# MegaShield-SMD.net
KiCad netlist of a schematic drawn in EAGLE
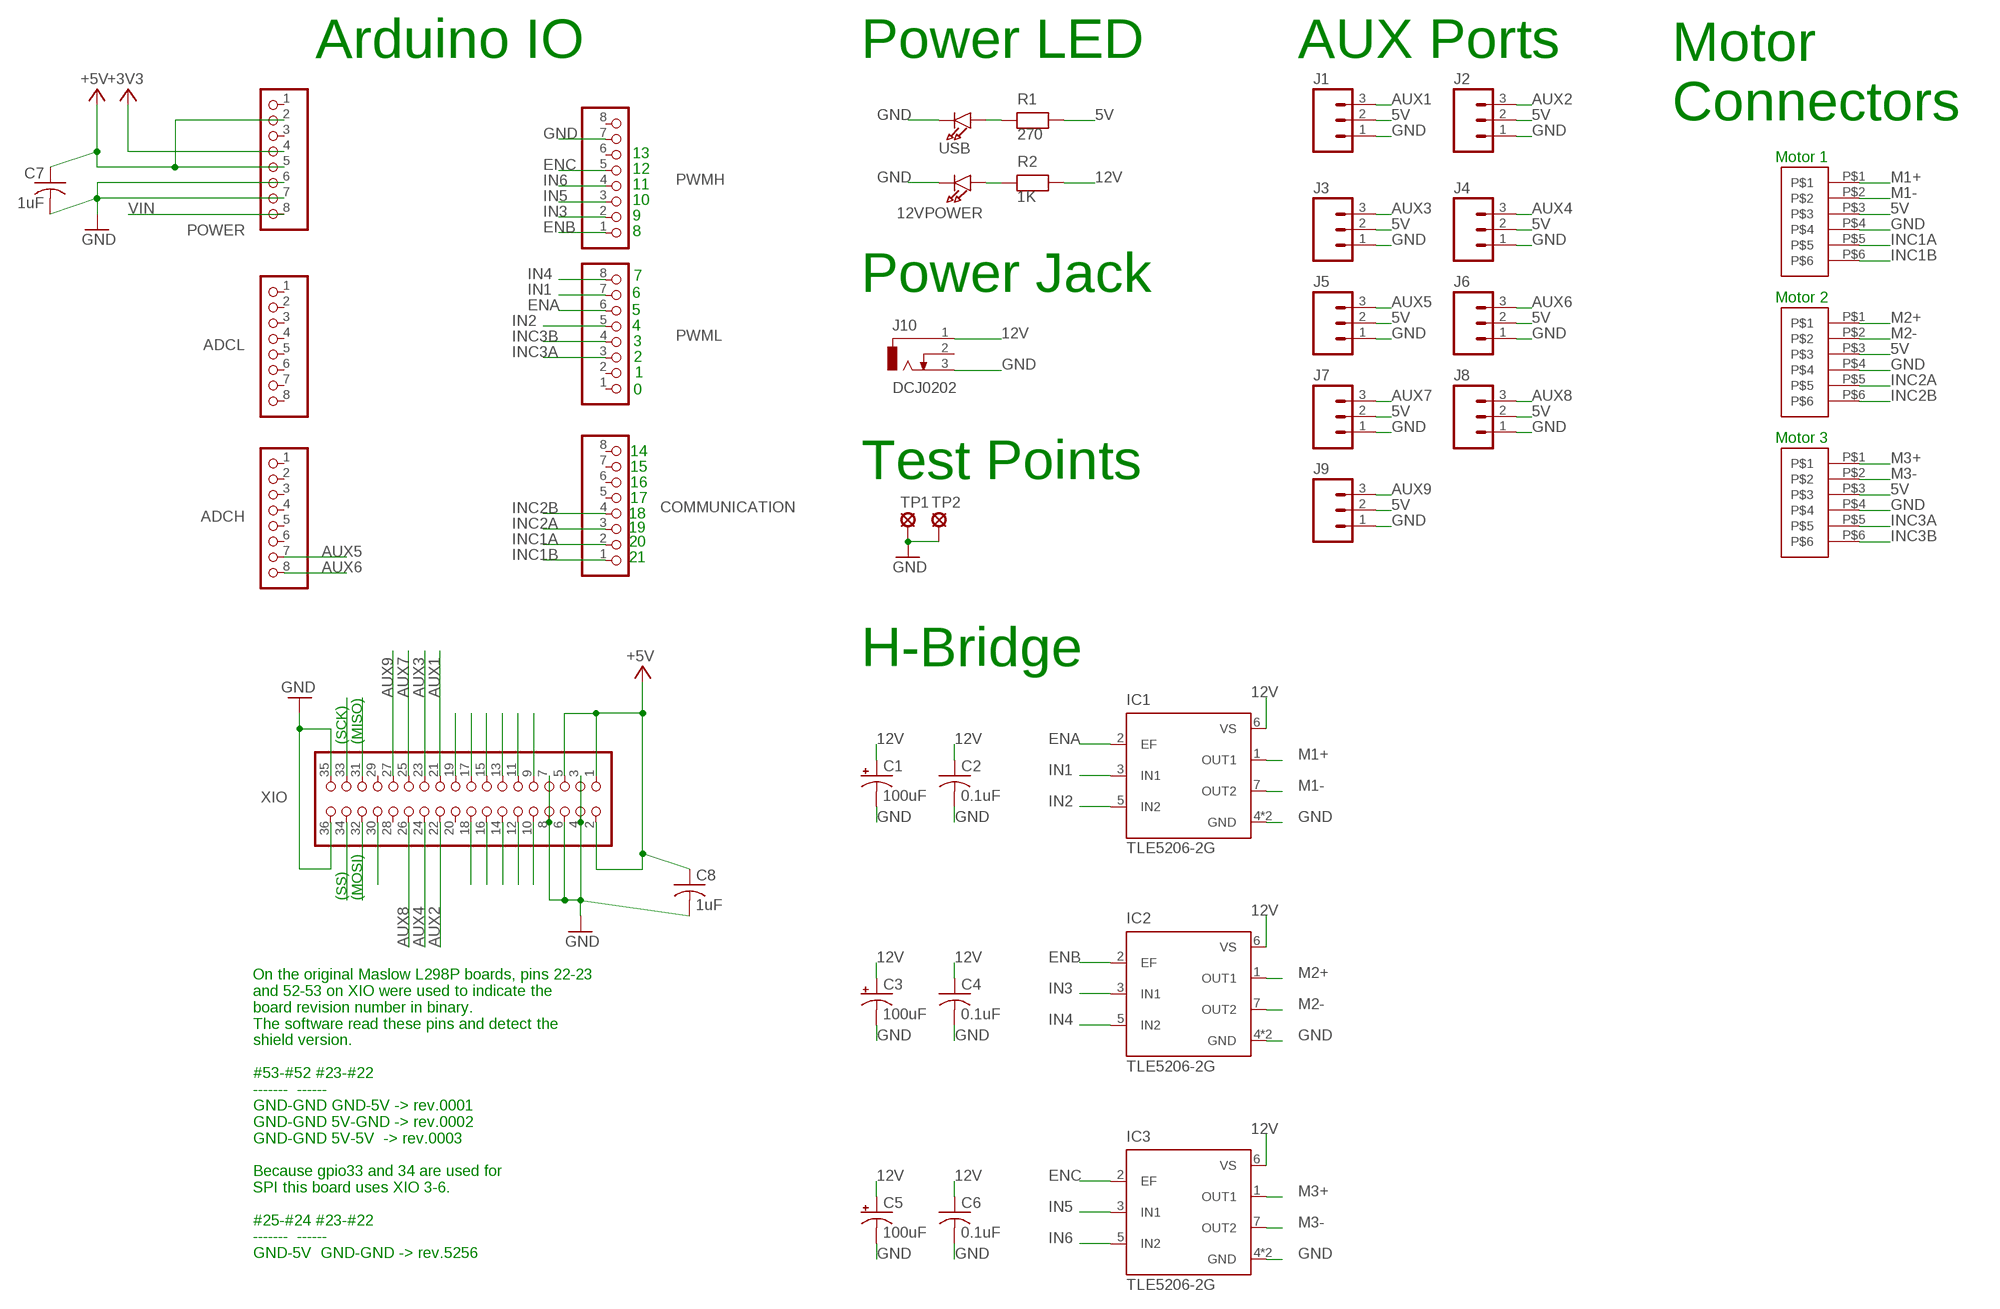
[diagram p0: schematic, sheet 1]

(export (version "E")
  (design (tool "Eeschema 10.0.6"))
  (components
    (comp (ref "12VPOWER")
      (value "LED1206")
      (footprint "eagle-import:CHIPLED_1206")
      (libsource (lib "eagle-import") (part "LED1206"))
    )
    (comp (ref "ADCH")
      (value "8x1F-H8.5")
      (footprint "eagle-import:1X08")
      (libsource (lib "eagle-import") (part "PINHD-1X8"))
    )
    (comp (ref "ADCL")
      (value "PINHD-1X8")
      (footprint "eagle-import:1X08")
      (libsource (lib "eagle-import") (part "pinhead_PINHD-1X8"))
    )
    (comp (ref "C1")
      (value "100uF")
      (footprint "eagle-import:PANASONIC_E")
      (libsource (lib "eagle-import") (part "CAP_POLE"))
    )
    (comp (ref "C2")
      (value "0.1uF")
      (footprint "eagle-import:C0805K")
      (libsource (lib "eagle-import") (part "C-USC0805K"))
    )
    (comp (ref "C3")
      (value "100uF")
      (footprint "eagle-import:PANASONIC_E")
      (libsource (lib "eagle-import") (part "CAP_POLE"))
    )
    (comp (ref "C4")
      (value "0.1uF")
      (footprint "eagle-import:C0805K")
      (libsource (lib "eagle-import") (part "C-USC0805K"))
    )
    (comp (ref "C5")
      (value "100uF")
      (footprint "eagle-import:PANASONIC_E")
      (libsource (lib "eagle-import") (part "CAP_POLE"))
    )
    (comp (ref "C6")
      (value "0.1uF")
      (footprint "eagle-import:C0805K")
      (libsource (lib "eagle-import") (part "C-USC0805K"))
    )
    (comp (ref "C7")
      (value "1uF")
      (footprint "eagle-import:C0805K")
      (libsource (lib "eagle-import") (part "C-USC0805K"))
    )
    (comp (ref "C8")
      (value "1uF")
      (footprint "eagle-import:C0805K")
      (libsource (lib "eagle-import") (part "C-USC0805K"))
    )
    (comp (ref "COMMUNICATION")
      (value "PINHD-1X8")
      (footprint "eagle-import:1X08")
      (libsource (lib "eagle-import") (part "pinhead_PINHD-1X8"))
    )
    (comp (ref "IC1")
      (value "TLE5206-2G")
      (footprint "eagle-import:INF-PG-TO263-7-1_L_1PRIMARY")
      (libsource (lib "eagle-import") (part "TLE5206-2G"))
    )
    (comp (ref "IC2")
      (value "TLE5206-2G")
      (footprint "eagle-import:INF-PG-TO263-7-1_L_1PRIMARY")
      (libsource (lib "eagle-import") (part "TLE5206-2G"))
    )
    (comp (ref "IC3")
      (value "TLE5206-2G")
      (footprint "eagle-import:INF-PG-TO263-7-1_L_1PRIMARY")
      (libsource (lib "eagle-import") (part "TLE5206-2G"))
    )
    (comp (ref "J1")
      (value "M03LOCK")
      (footprint "eagle-import:1X03_LOCK")
      (libsource (lib "eagle-import") (part "M03LOCK"))
    )
    (comp (ref "J2")
      (value "M03LOCK")
      (footprint "eagle-import:1X03_LOCK")
      (libsource (lib "eagle-import") (part "M03LOCK"))
    )
    (comp (ref "J3")
      (value "M03LOCK")
      (footprint "eagle-import:1X03_LOCK")
      (libsource (lib "eagle-import") (part "M03LOCK"))
    )
    (comp (ref "J4")
      (value "M03LOCK")
      (footprint "eagle-import:1X03_LOCK")
      (libsource (lib "eagle-import") (part "M03LOCK"))
    )
    (comp (ref "J5")
      (value "M03LOCK")
      (footprint "eagle-import:1X03_LOCK")
      (libsource (lib "eagle-import") (part "M03LOCK"))
    )
    (comp (ref "J6")
      (value "M03LOCK")
      (footprint "eagle-import:1X03_LOCK")
      (libsource (lib "eagle-import") (part "M03LOCK"))
    )
    (comp (ref "J7")
      (value "M03LOCK")
      (footprint "eagle-import:1X03_LOCK")
      (libsource (lib "eagle-import") (part "M03LOCK"))
    )
    (comp (ref "J8")
      (value "M03LOCK")
      (footprint "eagle-import:1X03_LOCK")
      (libsource (lib "eagle-import") (part "M03LOCK"))
    )
    (comp (ref "J9")
      (value "M03LOCK")
      (footprint "eagle-import:1X03_LOCK")
      (libsource (lib "eagle-import") (part "M03LOCK"))
    )
    (comp (ref "J10")
      (value "DCJ0202")
      (footprint "eagle-import:DCJ0202")
      (libsource (lib "eagle-import") (part "DCJ0202"))
    )
    (comp (ref "MP1")
      (value "JST-PH-6")
      (footprint "eagle-import:JST-PHR-6-SMD")
      (libsource (lib "eagle-import") (part "JST-PH-6"))
    )
    (comp (ref "MP2")
      (value "JST-PH-6")
      (footprint "eagle-import:JST-PHR-6-SMD")
      (libsource (lib "eagle-import") (part "JST-PH-6"))
    )
    (comp (ref "MP3")
      (value "JST-PH-6")
      (footprint "eagle-import:JST-PHR-6-SMD")
      (libsource (lib "eagle-import") (part "JST-PH-6"))
    )
    (comp (ref "POWER")
      (value "8x1F-H8.5")
      (footprint "eagle-import:1X08")
      (libsource (lib "eagle-import") (part "PINHD-1X8"))
    )
    (comp (ref "PWMH")
      (value "PINHD-1X8")
      (footprint "eagle-import:1X08")
      (libsource (lib "eagle-import") (part "pinhead_PINHD-1X8"))
    )
    (comp (ref "PWML")
      (value "PINHD-1X8")
      (footprint "eagle-import:1X08")
      (libsource (lib "eagle-import") (part "pinhead_PINHD-1X8"))
    )
    (comp (ref "R1")
      (value "270")
      (footprint "eagle-import:0805")
      (libsource (lib "eagle-import") (part "RESISTOR0805"))
    )
    (comp (ref "R2")
      (value "1K")
      (footprint "eagle-import:0805")
      (libsource (lib "eagle-import") (part "RESISTOR0805"))
    )
    (comp (ref "TP1")
      (value "LSP10")
      (footprint "eagle-import:LSP10")
      (libsource (lib "eagle-import") (part "LSP10"))
    )
    (comp (ref "TP2")
      (value "LSP10")
      (footprint "eagle-import:LSP10")
      (libsource (lib "eagle-import") (part "LSP10"))
    )
    (comp (ref "USB")
      (value "LED1206")
      (footprint "eagle-import:CHIPLED_1206")
      (libsource (lib "eagle-import") (part "LED1206"))
    )
    (comp (ref "XIO")
      (value "18x2F-H8.5")
      (footprint "eagle-import:2X18")
      (libsource (lib "eagle-import") (part "PINHD-2X18"))
    )
  )
  (nets
    (net (code "1") (name "+3V3") (class "Default")
      (node (ref "POWER") (pin "4") (pinfunction "4_4") (pintype "passive"))
    )
    (net (code "2") (name "+5V") (class "Default")
      (node (ref "C7") (pin "1") (pinfunction "1_1") (pintype "passive"))
      (node (ref "C8") (pin "1") (pinfunction "1_1") (pintype "passive"))
      (node (ref "J1") (pin "2") (pinfunction "2_2") (pintype "passive"))
      (node (ref "J2") (pin "2") (pinfunction "2_2") (pintype "passive"))
      (node (ref "J3") (pin "2") (pinfunction "2_2") (pintype "passive"))
      (node (ref "J4") (pin "2") (pinfunction "2_2") (pintype "passive"))
      (node (ref "J5") (pin "2") (pinfunction "2_2") (pintype "passive"))
      (node (ref "J6") (pin "2") (pinfunction "2_2") (pintype "passive"))
      (node (ref "J7") (pin "2") (pinfunction "2_2") (pintype "passive"))
      (node (ref "J8") (pin "2") (pinfunction "2_2") (pintype "passive"))
      (node (ref "J9") (pin "2") (pinfunction "2_2") (pintype "passive"))
      (node (ref "MP1") (pin "P$3") (pinfunction "P$3_P$3") (pintype "bidirectional"))
      (node (ref "MP2") (pin "P$3") (pinfunction "P$3_P$3") (pintype "bidirectional"))
      (node (ref "MP3") (pin "P$3") (pinfunction "P$3_P$3") (pintype "bidirectional"))
      (node (ref "POWER") (pin "2") (pinfunction "2_2") (pintype "passive"))
      (node (ref "POWER") (pin "5") (pinfunction "5_5") (pintype "passive"))
      (node (ref "R1") (pin "2") (pinfunction "2_2") (pintype "passive"))
      (node (ref "XIO") (pin "1") (pinfunction "1_1") (pintype "passive"))
      (node (ref "XIO") (pin "2") (pinfunction "2_2") (pintype "passive"))
      (node (ref "XIO") (pin "5") (pinfunction "5_5") (pintype "passive"))
    )
    (net (code "3") (name "/12V") (class "Default")
      (node (ref "C1") (pin "+") (pinfunction "+_+") (pintype "passive"))
      (node (ref "C2") (pin "1") (pinfunction "1_1") (pintype "passive"))
      (node (ref "C3") (pin "+") (pinfunction "+_+") (pintype "passive"))
      (node (ref "C4") (pin "1") (pinfunction "1_1") (pintype "passive"))
      (node (ref "C5") (pin "+") (pinfunction "+_+") (pintype "passive"))
      (node (ref "C6") (pin "1") (pinfunction "1_1") (pintype "passive"))
      (node (ref "IC1") (pin "6") (pinfunction "VS_6") (pintype "input"))
      (node (ref "IC2") (pin "6") (pinfunction "VS_6") (pintype "input"))
      (node (ref "IC3") (pin "6") (pinfunction "VS_6") (pintype "input"))
      (node (ref "J10") (pin "1") (pinfunction "1_1") (pintype "passive"))
      (node (ref "R2") (pin "2") (pinfunction "2_2") (pintype "passive"))
    )
    (net (code "4") (name "/AUX1") (class "Default")
      (node (ref "J1") (pin "3") (pinfunction "3_3") (pintype "passive"))
      (node (ref "XIO") (pin "21") (pinfunction "21_21") (pintype "passive"))
    )
    (net (code "5") (name "/AUX2") (class "Default")
      (node (ref "J2") (pin "3") (pinfunction "3_3") (pintype "passive"))
      (node (ref "XIO") (pin "22") (pinfunction "22_22") (pintype "passive"))
    )
    (net (code "6") (name "/AUX3") (class "Default")
      (node (ref "J3") (pin "3") (pinfunction "3_3") (pintype "passive"))
      (node (ref "XIO") (pin "23") (pinfunction "23_23") (pintype "passive"))
    )
    (net (code "7") (name "/AUX4") (class "Default")
      (node (ref "J4") (pin "3") (pinfunction "3_3") (pintype "passive"))
      (node (ref "XIO") (pin "24") (pinfunction "24_24") (pintype "passive"))
    )
    (net (code "8") (name "/AUX5") (class "Default")
      (node (ref "ADCH") (pin "7") (pinfunction "7_7") (pintype "passive"))
      (node (ref "J5") (pin "3") (pinfunction "3_3") (pintype "passive"))
    )
    (net (code "9") (name "/AUX6") (class "Default")
      (node (ref "ADCH") (pin "8") (pinfunction "8_8") (pintype "passive"))
      (node (ref "J6") (pin "3") (pinfunction "3_3") (pintype "passive"))
    )
    (net (code "10") (name "/AUX7") (class "Default")
      (node (ref "J7") (pin "3") (pinfunction "3_3") (pintype "passive"))
      (node (ref "XIO") (pin "25") (pinfunction "25_25") (pintype "passive"))
    )
    (net (code "11") (name "/AUX8") (class "Default")
      (node (ref "J8") (pin "3") (pinfunction "3_3") (pintype "passive"))
      (node (ref "XIO") (pin "26") (pinfunction "26_26") (pintype "passive"))
    )
    (net (code "12") (name "/AUX9") (class "Default")
      (node (ref "J9") (pin "3") (pinfunction "3_3") (pintype "passive"))
      (node (ref "XIO") (pin "27") (pinfunction "27_27") (pintype "passive"))
    )
    (net (code "13") (name "/ENA") (class "Default")
      (node (ref "IC1") (pin "2") (pinfunction "EF_2") (pintype "open_collector"))
      (node (ref "PWML") (pin "6") (pinfunction "6_6") (pintype "passive"))
    )
    (net (code "14") (name "/ENB") (class "Default")
      (node (ref "IC2") (pin "2") (pinfunction "EF_2") (pintype "open_collector"))
      (node (ref "PWMH") (pin "1") (pinfunction "1_1") (pintype "passive"))
    )
    (net (code "15") (name "/ENC") (class "Default")
      (node (ref "IC3") (pin "2") (pinfunction "EF_2") (pintype "open_collector"))
      (node (ref "PWMH") (pin "5") (pinfunction "5_5") (pintype "passive"))
    )
    (net (code "16") (name "/IN1") (class "Default")
      (node (ref "IC1") (pin "3") (pinfunction "IN1_3") (pintype "input"))
      (node (ref "PWML") (pin "7") (pinfunction "7_7") (pintype "passive"))
    )
    (net (code "17") (name "/IN2") (class "Default")
      (node (ref "IC1") (pin "5") (pinfunction "IN2_5") (pintype "input"))
      (node (ref "PWML") (pin "5") (pinfunction "5_5") (pintype "passive"))
    )
    (net (code "18") (name "/IN3") (class "Default")
      (node (ref "IC2") (pin "3") (pinfunction "IN1_3") (pintype "input"))
      (node (ref "PWMH") (pin "2") (pinfunction "2_2") (pintype "passive"))
    )
    (net (code "19") (name "/IN4") (class "Default")
      (node (ref "IC2") (pin "5") (pinfunction "IN2_5") (pintype "input"))
      (node (ref "PWML") (pin "8") (pinfunction "8_8") (pintype "passive"))
    )
    (net (code "20") (name "/IN5") (class "Default")
      (node (ref "IC3") (pin "3") (pinfunction "IN1_3") (pintype "input"))
      (node (ref "PWMH") (pin "3") (pinfunction "3_3") (pintype "passive"))
    )
    (net (code "21") (name "/IN6") (class "Default")
      (node (ref "IC3") (pin "5") (pinfunction "IN2_5") (pintype "input"))
      (node (ref "PWMH") (pin "4") (pinfunction "4_4") (pintype "passive"))
    )
    (net (code "22") (name "/INC1A") (class "Default")
      (node (ref "COMMUNICATION") (pin "2") (pinfunction "2_2") (pintype "passive"))
      (node (ref "MP1") (pin "P$5") (pinfunction "P$5_P$5") (pintype "bidirectional"))
    )
    (net (code "23") (name "/INC1B") (class "Default")
      (node (ref "COMMUNICATION") (pin "1") (pinfunction "1_1") (pintype "passive"))
      (node (ref "MP1") (pin "P$6") (pinfunction "P$6_P$6") (pintype "bidirectional"))
    )
    (net (code "24") (name "/INC2A") (class "Default")
      (node (ref "COMMUNICATION") (pin "3") (pinfunction "3_3") (pintype "passive"))
      (node (ref "MP2") (pin "P$5") (pinfunction "P$5_P$5") (pintype "bidirectional"))
    )
    (net (code "25") (name "/INC2B") (class "Default")
      (node (ref "COMMUNICATION") (pin "4") (pinfunction "4_4") (pintype "passive"))
      (node (ref "MP2") (pin "P$6") (pinfunction "P$6_P$6") (pintype "bidirectional"))
    )
    (net (code "26") (name "/INC3A") (class "Default")
      (node (ref "MP3") (pin "P$5") (pinfunction "P$5_P$5") (pintype "bidirectional"))
      (node (ref "PWML") (pin "3") (pinfunction "3_3") (pintype "passive"))
    )
    (net (code "27") (name "/INC3B") (class "Default")
      (node (ref "MP3") (pin "P$6") (pinfunction "P$6_P$6") (pintype "bidirectional"))
      (node (ref "PWML") (pin "4") (pinfunction "4_4") (pintype "passive"))
    )
    (net (code "28") (name "/M1+") (class "Default")
      (node (ref "IC1") (pin "1") (pinfunction "OUT1_1") (pintype "output"))
      (node (ref "MP1") (pin "P$1") (pinfunction "P$1_P$1") (pintype "bidirectional"))
    )
    (net (code "29") (name "/M1-") (class "Default")
      (node (ref "IC1") (pin "7") (pinfunction "OUT2_7") (pintype "output"))
      (node (ref "MP1") (pin "P$2") (pinfunction "P$2_P$2") (pintype "bidirectional"))
    )
    (net (code "30") (name "/M2+") (class "Default")
      (node (ref "IC2") (pin "1") (pinfunction "OUT1_1") (pintype "output"))
      (node (ref "MP2") (pin "P$1") (pinfunction "P$1_P$1") (pintype "bidirectional"))
    )
    (net (code "31") (name "/M2-") (class "Default")
      (node (ref "IC2") (pin "7") (pinfunction "OUT2_7") (pintype "output"))
      (node (ref "MP2") (pin "P$2") (pinfunction "P$2_P$2") (pintype "bidirectional"))
    )
    (net (code "32") (name "/M3+") (class "Default")
      (node (ref "IC3") (pin "1") (pinfunction "OUT1_1") (pintype "output"))
      (node (ref "MP3") (pin "P$1") (pinfunction "P$1_P$1") (pintype "bidirectional"))
    )
    (net (code "33") (name "/M3-") (class "Default")
      (node (ref "IC3") (pin "7") (pinfunction "OUT2_7") (pintype "output"))
      (node (ref "MP3") (pin "P$2") (pinfunction "P$2_P$2") (pintype "bidirectional"))
    )
    (net (code "34") (name "/VIN") (class "Default")
      (node (ref "POWER") (pin "8") (pinfunction "8_8") (pintype "passive"))
    )
    (net (code "35") (name "GND") (class "Default")
      (node (ref "12VPOWER") (pin "C") (pinfunction "C_C") (pintype "passive"))
      (node (ref "C1") (pin "-") (pinfunction "-_-") (pintype "passive"))
      (node (ref "C2") (pin "2") (pinfunction "2_2") (pintype "passive"))
      (node (ref "C3") (pin "-") (pinfunction "-_-") (pintype "passive"))
      (node (ref "C4") (pin "2") (pinfunction "2_2") (pintype "passive"))
      (node (ref "C5") (pin "-") (pinfunction "-_-") (pintype "passive"))
      (node (ref "C6") (pin "2") (pinfunction "2_2") (pintype "passive"))
      (node (ref "C7") (pin "2") (pinfunction "2_2") (pintype "passive"))
      (node (ref "C8") (pin "2") (pinfunction "2_2") (pintype "passive"))
      (node (ref "IC1") (pin "4") (pinfunction "GND_4") (pintype "power_in"))
      (node (ref "IC1") (pin "8") (pinfunction "GND_8") (pintype "power_in"))
      (node (ref "IC2") (pin "4") (pinfunction "GND_4") (pintype "power_in"))
      (node (ref "IC2") (pin "8") (pinfunction "GND_8") (pintype "power_in"))
      (node (ref "IC3") (pin "4") (pinfunction "GND_4") (pintype "power_in"))
      (node (ref "IC3") (pin "8") (pinfunction "GND_8") (pintype "power_in"))
      (node (ref "J1") (pin "1") (pinfunction "1_1") (pintype "passive"))
      (node (ref "J10") (pin "3") (pinfunction "3_3") (pintype "passive"))
      (node (ref "J2") (pin "1") (pinfunction "1_1") (pintype "passive"))
      (node (ref "J3") (pin "1") (pinfunction "1_1") (pintype "passive"))
      (node (ref "J4") (pin "1") (pinfunction "1_1") (pintype "passive"))
      (node (ref "J5") (pin "1") (pinfunction "1_1") (pintype "passive"))
      (node (ref "J6") (pin "1") (pinfunction "1_1") (pintype "passive"))
      (node (ref "J7") (pin "1") (pinfunction "1_1") (pintype "passive"))
      (node (ref "J8") (pin "1") (pinfunction "1_1") (pintype "passive"))
      (node (ref "J9") (pin "1") (pinfunction "1_1") (pintype "passive"))
      (node (ref "MP1") (pin "P$4") (pinfunction "P$4_P$4") (pintype "bidirectional"))
      (node (ref "MP2") (pin "P$4") (pinfunction "P$4_P$4") (pintype "bidirectional"))
      (node (ref "MP3") (pin "P$4") (pinfunction "P$4_P$4") (pintype "bidirectional"))
      (node (ref "POWER") (pin "6") (pinfunction "6_6") (pintype "passive"))
      (node (ref "POWER") (pin "7") (pinfunction "7_7") (pintype "passive"))
      (node (ref "PWMH") (pin "7") (pinfunction "7_7") (pintype "passive"))
      (node (ref "TP1") (pin "MP") (pinfunction "MP_MP") (pintype "passive"))
      (node (ref "TP2") (pin "MP") (pinfunction "MP_MP") (pintype "passive"))
      (node (ref "USB") (pin "C") (pinfunction "C_C") (pintype "passive"))
      (node (ref "XIO") (pin "3") (pinfunction "3_3") (pintype "passive"))
      (node (ref "XIO") (pin "35") (pinfunction "35_35") (pintype "passive"))
      (node (ref "XIO") (pin "36") (pinfunction "36_36") (pintype "passive"))
      (node (ref "XIO") (pin "4") (pinfunction "4_4") (pintype "passive"))
      (node (ref "XIO") (pin "6") (pinfunction "6_6") (pintype "passive"))
      (node (ref "XIO") (pin "7") (pinfunction "7_7") (pintype "passive"))
      (node (ref "XIO") (pin "8") (pinfunction "8_8") (pintype "passive"))
    )
    (net (code "36") (name "Net-(12VPOWER-PadA)") (class "Default")
      (node (ref "12VPOWER") (pin "A") (pinfunction "A_A") (pintype "passive"))
      (node (ref "R2") (pin "1") (pinfunction "1_1") (pintype "passive"))
    )
    (net (code "37") (name "Net-(R1-Pad1)") (class "Default")
      (node (ref "R1") (pin "1") (pinfunction "1_1") (pintype "passive"))
      (node (ref "USB") (pin "A") (pinfunction "A_A") (pintype "passive"))
    )
    (net (code "38") (name "unconnected-(ADCH-Pad1)") (class "Default")
      (node (ref "ADCH") (pin "1") (pinfunction "1_1") (pintype "passive"))
    )
    (net (code "39") (name "unconnected-(ADCH-Pad2)") (class "Default")
      (node (ref "ADCH") (pin "2") (pinfunction "2_2") (pintype "passive"))
    )
    (net (code "40") (name "unconnected-(ADCH-Pad3)") (class "Default")
      (node (ref "ADCH") (pin "3") (pinfunction "3_3") (pintype "passive"))
    )
    (net (code "41") (name "unconnected-(ADCH-Pad4)") (class "Default")
      (node (ref "ADCH") (pin "4") (pinfunction "4_4") (pintype "passive"))
    )
    (net (code "42") (name "unconnected-(ADCH-Pad5)") (class "Default")
      (node (ref "ADCH") (pin "5") (pinfunction "5_5") (pintype "passive"))
    )
    (net (code "43") (name "unconnected-(ADCH-Pad6)") (class "Default")
      (node (ref "ADCH") (pin "6") (pinfunction "6_6") (pintype "passive"))
    )
    (net (code "44") (name "unconnected-(ADCL-Pad1)") (class "Default")
      (node (ref "ADCL") (pin "1") (pinfunction "1_1") (pintype "passive"))
    )
    (net (code "45") (name "unconnected-(ADCL-Pad2)") (class "Default")
      (node (ref "ADCL") (pin "2") (pinfunction "2_2") (pintype "passive"))
    )
    (net (code "46") (name "unconnected-(ADCL-Pad3)") (class "Default")
      (node (ref "ADCL") (pin "3") (pinfunction "3_3") (pintype "passive"))
    )
    (net (code "47") (name "unconnected-(ADCL-Pad4)") (class "Default")
      (node (ref "ADCL") (pin "4") (pinfunction "4_4") (pintype "passive"))
    )
    (net (code "48") (name "unconnected-(ADCL-Pad5)") (class "Default")
      (node (ref "ADCL") (pin "5") (pinfunction "5_5") (pintype "passive"))
    )
    (net (code "49") (name "unconnected-(ADCL-Pad6)") (class "Default")
      (node (ref "ADCL") (pin "6") (pinfunction "6_6") (pintype "passive"))
    )
    (net (code "50") (name "unconnected-(ADCL-Pad7)") (class "Default")
      (node (ref "ADCL") (pin "7") (pinfunction "7_7") (pintype "passive"))
    )
    (net (code "51") (name "unconnected-(ADCL-Pad8)") (class "Default")
      (node (ref "ADCL") (pin "8") (pinfunction "8_8") (pintype "passive"))
    )
    (net (code "52") (name "unconnected-(COMMUNICATION-Pad5)") (class "Default")
      (node (ref "COMMUNICATION") (pin "5") (pinfunction "5_5") (pintype "passive"))
    )
    (net (code "53") (name "unconnected-(COMMUNICATION-Pad6)") (class "Default")
      (node (ref "COMMUNICATION") (pin "6") (pinfunction "6_6") (pintype "passive"))
    )
    (net (code "54") (name "unconnected-(COMMUNICATION-Pad7)") (class "Default")
      (node (ref "COMMUNICATION") (pin "7") (pinfunction "7_7") (pintype "passive"))
    )
    (net (code "55") (name "unconnected-(COMMUNICATION-Pad8)") (class "Default")
      (node (ref "COMMUNICATION") (pin "8") (pinfunction "8_8") (pintype "passive"))
    )
    (net (code "56") (name "unconnected-(J10-Pad2)") (class "Default")
      (node (ref "J10") (pin "2") (pinfunction "2_2") (pintype "passive"))
    )
    (net (code "57") (name "unconnected-(POWER-Pad1)") (class "Default")
      (node (ref "POWER") (pin "1") (pinfunction "1_1") (pintype "passive"))
    )
    (net (code "58") (name "unconnected-(POWER-Pad3)") (class "Default")
      (node (ref "POWER") (pin "3") (pinfunction "3_3") (pintype "passive"))
    )
    (net (code "59") (name "unconnected-(PWMH-Pad6)") (class "Default")
      (node (ref "PWMH") (pin "6") (pinfunction "6_6") (pintype "passive"))
    )
    (net (code "60") (name "unconnected-(PWMH-Pad8)") (class "Default")
      (node (ref "PWMH") (pin "8") (pinfunction "8_8") (pintype "passive"))
    )
    (net (code "61") (name "unconnected-(PWML-Pad1)") (class "Default")
      (node (ref "PWML") (pin "1") (pinfunction "1_1") (pintype "passive"))
    )
    (net (code "62") (name "unconnected-(PWML-Pad2)") (class "Default")
      (node (ref "PWML") (pin "2") (pinfunction "2_2") (pintype "passive"))
    )
    (net (code "63") (name "unconnected-(XIO-Pad9)") (class "Default")
      (node (ref "XIO") (pin "9") (pinfunction "9_9") (pintype "passive"))
    )
    (net (code "64") (name "unconnected-(XIO-Pad10)") (class "Default")
      (node (ref "XIO") (pin "10") (pinfunction "10_10") (pintype "passive"))
    )
    (net (code "65") (name "unconnected-(XIO-Pad11)") (class "Default")
      (node (ref "XIO") (pin "11") (pinfunction "11_11") (pintype "passive"))
    )
    (net (code "66") (name "unconnected-(XIO-Pad12)") (class "Default")
      (node (ref "XIO") (pin "12") (pinfunction "12_12") (pintype "passive"))
    )
    (net (code "67") (name "unconnected-(XIO-Pad13)") (class "Default")
      (node (ref "XIO") (pin "13") (pinfunction "13_13") (pintype "passive"))
    )
    (net (code "68") (name "unconnected-(XIO-Pad14)") (class "Default")
      (node (ref "XIO") (pin "14") (pinfunction "14_14") (pintype "passive"))
    )
    (net (code "69") (name "unconnected-(XIO-Pad15)") (class "Default")
      (node (ref "XIO") (pin "15") (pinfunction "15_15") (pintype "passive"))
    )
    (net (code "70") (name "unconnected-(XIO-Pad16)") (class "Default")
      (node (ref "XIO") (pin "16") (pinfunction "16_16") (pintype "passive"))
    )
    (net (code "71") (name "unconnected-(XIO-Pad17)") (class "Default")
      (node (ref "XIO") (pin "17") (pinfunction "17_17") (pintype "passive"))
    )
    (net (code "72") (name "unconnected-(XIO-Pad18)") (class "Default")
      (node (ref "XIO") (pin "18") (pinfunction "18_18") (pintype "passive"))
    )
    (net (code "73") (name "unconnected-(XIO-Pad19)") (class "Default")
      (node (ref "XIO") (pin "19") (pinfunction "19_19") (pintype "passive"))
    )
    (net (code "74") (name "unconnected-(XIO-Pad20)") (class "Default")
      (node (ref "XIO") (pin "20") (pinfunction "20_20") (pintype "passive"))
    )
    (net (code "75") (name "unconnected-(XIO-Pad28)") (class "Default")
      (node (ref "XIO") (pin "28") (pinfunction "28_28") (pintype "passive"))
    )
    (net (code "76") (name "unconnected-(XIO-Pad29)") (class "Default")
      (node (ref "XIO") (pin "29") (pinfunction "29_29") (pintype "passive"))
    )
    (net (code "77") (name "unconnected-(XIO-Pad30)") (class "Default")
      (node (ref "XIO") (pin "30") (pinfunction "30_30") (pintype "passive"))
    )
    (net (code "78") (name "unconnected-(XIO-Pad31)") (class "Default")
      (node (ref "XIO") (pin "31") (pinfunction "31_31") (pintype "passive"))
    )
    (net (code "79") (name "unconnected-(XIO-Pad32)") (class "Default")
      (node (ref "XIO") (pin "32") (pinfunction "32_32") (pintype "passive"))
    )
    (net (code "80") (name "unconnected-(XIO-Pad33)") (class "Default")
      (node (ref "XIO") (pin "33") (pinfunction "33_33") (pintype "passive"))
    )
    (net (code "81") (name "unconnected-(XIO-Pad34)") (class "Default")
      (node (ref "XIO") (pin "34") (pinfunction "34_34") (pintype "passive"))
    )
  )
)
